# controlador_automa_o_granja.net
KiCad netlist of a schematic drawn in EAGLE
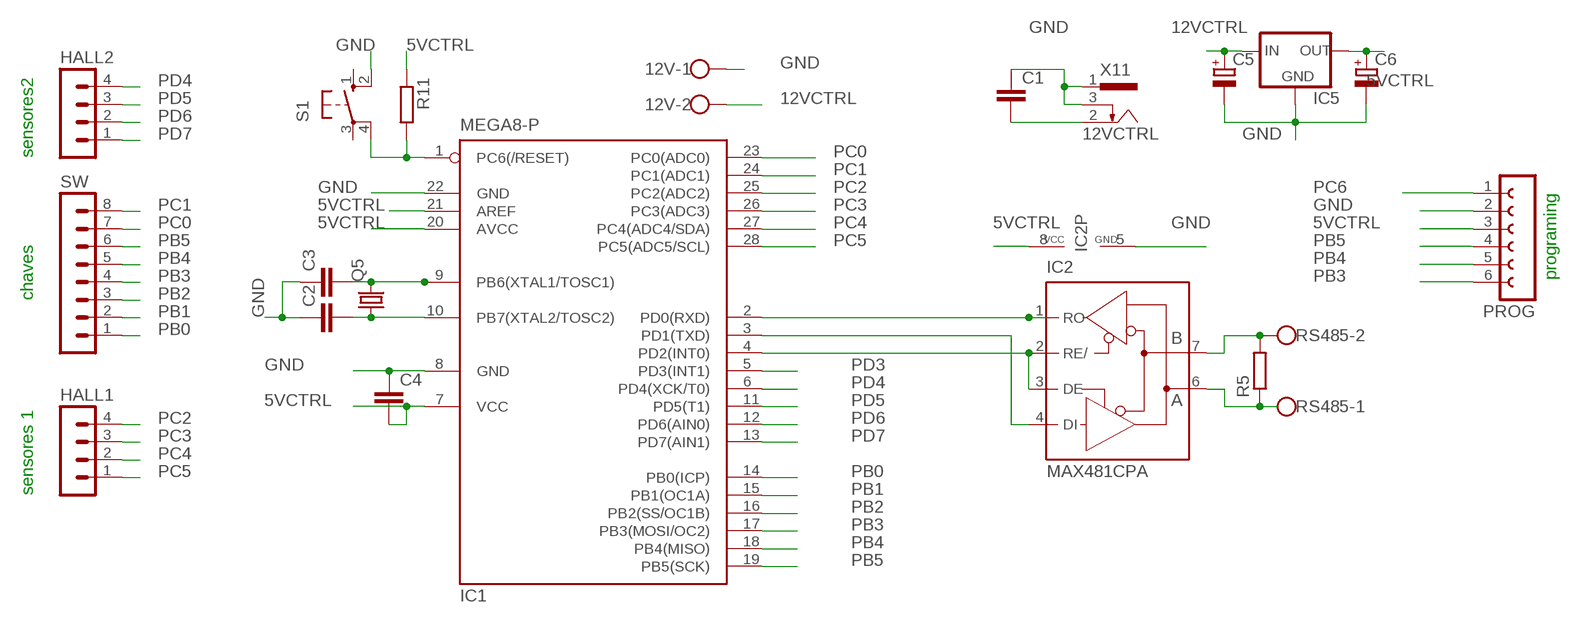
[diagram p0: schematic, sheet 1]

(export (version "E")
  (design (tool "Eeschema 10.0.6"))
  (components
    (comp (ref "12V")
      (value "W237-102")
      (footprint "eagle-import:W237-102")
      (fields (field (name "MPN") "237-102"))
      (libsource (lib "eagle-import") (part "W237-102"))
    )
    (comp (ref "C1")
      (value "C-EU050-025X075")
      (footprint "eagle-import:C050-025X075")
      (libsource (lib "eagle-import") (part "C-EU050-025X075"))
    )
    (comp (ref "C2")
      (value "C-EU050-025X075")
      (footprint "eagle-import:C050-025X075")
      (libsource (lib "eagle-import") (part "C-EU050-025X075"))
    )
    (comp (ref "C3")
      (value "C-EU050-024X044")
      (footprint "eagle-import:C050-024X044")
      (libsource (lib "eagle-import") (part "C-EU050-024X044"))
    )
    (comp (ref "C4")
      (value "C-EU050-024X044")
      (footprint "eagle-import:C050-024X044")
      (libsource (lib "eagle-import") (part "resistor_C-EU050-024X044"))
    )
    (comp (ref "C5")
      (value "CPOL-EUE1.8-4")
      (footprint "eagle-import:E1,8-4")
      (libsource (lib "eagle-import") (part "CPOL-EUE1.8-4"))
    )
    (comp (ref "C6")
      (value "CPOL-EUE1.8-4")
      (footprint "eagle-import:E1,8-4")
      (libsource (lib "eagle-import") (part "CPOL-EUE1.8-4"))
    )
    (comp (ref "HALL1")
      (value "MA04-1")
      (footprint "eagle-import:MA04-1")
      (libsource (lib "eagle-import") (part "MA04-1"))
    )
    (comp (ref "HALL2")
      (value "MA04-1")
      (footprint "eagle-import:MA04-1")
      (libsource (lib "eagle-import") (part "MA04-1"))
    )
    (comp (ref "IC1")
      (value "MEGA8-P")
      (footprint "eagle-import:DIL28-3")
      (libsource (lib "eagle-import") (part "MEGA8-P"))
    )
    (comp (ref "IC2")
      (value "MAX481CPA")
      (footprint "eagle-import:DIL08")
      (fields (field (name "MPN") "MAX481CPA+"))
      (libsource (lib "eagle-import") (part "MAX481CPA"))
    )
    (comp (ref "IC5")
      (value "78LXX")
      (footprint "eagle-import:78LXX")
      (libsource (lib "eagle-import") (part "78LXX"))
    )
    (comp (ref "PROG")
      (value "FE06-1")
      (footprint "eagle-import:FE06")
      (libsource (lib "eagle-import") (part "FE06-1"))
    )
    (comp (ref "Q5")
      (value "CRYSTALHC49S")
      (footprint "eagle-import:HC49_S")
      (libsource (lib "eagle-import") (part "CRYSTALHC49S"))
    )
    (comp (ref "R5")
      (value "R-EU_0207/7")
      (footprint "eagle-import:0207_7")
      (libsource (lib "eagle-import") (part "R-EU_0207/7"))
    )
    (comp (ref "R11")
      (value "R-EU_0207/7")
      (footprint "eagle-import:0207_7")
      (libsource (lib "eagle-import") (part "R-EU_0207/7"))
    )
    (comp (ref "RS485")
      (value "W237-102")
      (footprint "eagle-import:W237-102")
      (fields (field (name "MPN") "237-102"))
      (libsource (lib "eagle-import") (part "W237-102"))
    )
    (comp (ref "S1")
      (value "10-XX")
      (footprint "eagle-import:B3F-10XX")
      (fields (field (name "MPN") "B3F-1000"))
      (libsource (lib "eagle-import") (part "10-XX"))
    )
    (comp (ref "SW")
      (value "MA08-1")
      (footprint "eagle-import:MA08-1")
      (libsource (lib "eagle-import") (part "MA08-1"))
    )
    (comp (ref "X11")
      (value "733980-62")
      (footprint "eagle-import:733980-62")
      (libsource (lib "eagle-import") (part "73398?0-62"))
    )
  )
  (nets
    (net (code "1") (name "/5VCTRL") (class "Default")
      (node (ref "C4") (pin "2") (pinfunction "2_2") (pintype "passive"))
      (node (ref "C6") (pin "+") (pinfunction "+_+") (pintype "passive"))
      (node (ref "IC1") (pin "20") (pinfunction "AVCC_20") (pintype "power_in"))
      (node (ref "IC1") (pin "21") (pinfunction "AREF_21") (pintype "passive"))
      (node (ref "IC1") (pin "7") (pinfunction "VCC_7") (pintype "power_in"))
      (node (ref "IC2") (pin "8") (pinfunction "VCC_8") (pintype "power_in"))
      (node (ref "IC5") (pin "OUT") (pinfunction "OUT_OUT") (pintype "passive"))
      (node (ref "PROG") (pin "3") (pinfunction "3_3") (pintype "passive"))
      (node (ref "R11") (pin "1") (pinfunction "1_1") (pintype "passive"))
    )
    (net (code "2") (name "/12VCTRL") (class "Default")
      (node (ref "12V") (pin "2") (pinfunction "KL_2") (pintype "passive"))
      (node (ref "C1") (pin "2") (pinfunction "2_2") (pintype "passive"))
      (node (ref "C5") (pin "+") (pinfunction "+_+") (pintype "passive"))
      (node (ref "IC5") (pin "IN") (pinfunction "IN_IN") (pintype "input"))
      (node (ref "X11") (pin "2") (pinfunction "2_2") (pintype "passive"))
    )
    (net (code "3") (name "/GND") (class "Default")
      (node (ref "12V") (pin "1") (pinfunction "KL_1") (pintype "passive"))
      (node (ref "C1") (pin "1") (pinfunction "1_1") (pintype "passive"))
      (node (ref "C2") (pin "1") (pinfunction "1_1") (pintype "passive"))
      (node (ref "C3") (pin "1") (pinfunction "1_1") (pintype "passive"))
      (node (ref "C4") (pin "1") (pinfunction "1_1") (pintype "passive"))
      (node (ref "C5") (pin "-") (pinfunction "-_-") (pintype "passive"))
      (node (ref "C6") (pin "-") (pinfunction "-_-") (pintype "passive"))
      (node (ref "IC1") (pin "22") (pinfunction "GND_22") (pintype "power_in"))
      (node (ref "IC1") (pin "8") (pinfunction "GND_8") (pintype "power_in"))
      (node (ref "IC2") (pin "5") (pinfunction "GND_5") (pintype "power_in"))
      (node (ref "IC5") (pin "GND") (pinfunction "GND_GND") (pintype "input"))
      (node (ref "PROG") (pin "2") (pinfunction "2_2") (pintype "passive"))
      (node (ref "S1") (pin "2") (pinfunction "S1_2") (pintype "passive"))
      (node (ref "X11") (pin "1") (pinfunction "1_1") (pintype "passive"))
      (node (ref "X11") (pin "3") (pinfunction "3_3") (pintype "passive"))
    )
    (net (code "4") (name "/PB0") (class "Default")
      (node (ref "IC1") (pin "14") (pinfunction "PB0(ICP)_14") (pintype "bidirectional"))
      (node (ref "SW") (pin "1") (pinfunction "1_1") (pintype "passive"))
    )
    (net (code "5") (name "/PB1") (class "Default")
      (node (ref "IC1") (pin "15") (pinfunction "PB1(OC1A)_15") (pintype "bidirectional"))
      (node (ref "SW") (pin "2") (pinfunction "2_2") (pintype "passive"))
    )
    (net (code "6") (name "/PB2") (class "Default")
      (node (ref "IC1") (pin "16") (pinfunction "PB2(SS/OC1B)_16") (pintype "bidirectional"))
      (node (ref "SW") (pin "3") (pinfunction "3_3") (pintype "passive"))
    )
    (net (code "7") (name "/PB3") (class "Default")
      (node (ref "IC1") (pin "17") (pinfunction "PB3(MOSI/OC2)_17") (pintype "bidirectional"))
      (node (ref "PROG") (pin "6") (pinfunction "6_6") (pintype "passive"))
      (node (ref "SW") (pin "4") (pinfunction "4_4") (pintype "passive"))
    )
    (net (code "8") (name "/PB4") (class "Default")
      (node (ref "IC1") (pin "18") (pinfunction "PB4(MISO)_18") (pintype "bidirectional"))
      (node (ref "PROG") (pin "5") (pinfunction "5_5") (pintype "passive"))
      (node (ref "SW") (pin "5") (pinfunction "5_5") (pintype "passive"))
    )
    (net (code "9") (name "/PB5") (class "Default")
      (node (ref "IC1") (pin "19") (pinfunction "PB5(SCK)_19") (pintype "bidirectional"))
      (node (ref "PROG") (pin "4") (pinfunction "4_4") (pintype "passive"))
      (node (ref "SW") (pin "6") (pinfunction "6_6") (pintype "passive"))
    )
    (net (code "10") (name "/PC0") (class "Default")
      (node (ref "IC1") (pin "23") (pinfunction "PC0(ADC0)_23") (pintype "bidirectional"))
      (node (ref "SW") (pin "7") (pinfunction "7_7") (pintype "passive"))
    )
    (net (code "11") (name "/PC1") (class "Default")
      (node (ref "IC1") (pin "24") (pinfunction "PC1(ADC1)_24") (pintype "bidirectional"))
      (node (ref "SW") (pin "8") (pinfunction "8_8") (pintype "passive"))
    )
    (net (code "12") (name "/PC2") (class "Default")
      (node (ref "HALL1") (pin "4") (pinfunction "4_4") (pintype "passive"))
      (node (ref "IC1") (pin "25") (pinfunction "PC2(ADC2)_25") (pintype "bidirectional"))
    )
    (net (code "13") (name "/PC3") (class "Default")
      (node (ref "HALL1") (pin "3") (pinfunction "3_3") (pintype "passive"))
      (node (ref "IC1") (pin "26") (pinfunction "PC3(ADC3)_26") (pintype "bidirectional"))
    )
    (net (code "14") (name "/PC4") (class "Default")
      (node (ref "HALL1") (pin "2") (pinfunction "2_2") (pintype "passive"))
      (node (ref "IC1") (pin "27") (pinfunction "PC4(ADC4/SDA)_27") (pintype "bidirectional"))
    )
    (net (code "15") (name "/PC5") (class "Default")
      (node (ref "HALL1") (pin "1") (pinfunction "1_1") (pintype "passive"))
      (node (ref "IC1") (pin "28") (pinfunction "PC5(ADC5/SCL)_28") (pintype "bidirectional"))
    )
    (net (code "16") (name "/PC6") (class "Default")
      (node (ref "IC1") (pin "1") (pinfunction "PC6(/RESET)_1") (pintype "bidirectional"))
      (node (ref "PROG") (pin "1") (pinfunction "1_1") (pintype "passive"))
      (node (ref "R11") (pin "2") (pinfunction "2_2") (pintype "passive"))
      (node (ref "S1") (pin "4") (pinfunction "P1_4") (pintype "passive"))
    )
    (net (code "17") (name "/PD3") (class "Default")
      (node (ref "IC1") (pin "5") (pinfunction "PD3(INT1)_5") (pintype "bidirectional"))
    )
    (net (code "18") (name "/PD4") (class "Default")
      (node (ref "HALL2") (pin "4") (pinfunction "4_4") (pintype "passive"))
      (node (ref "IC1") (pin "6") (pinfunction "PD4(XCK/T0)_6") (pintype "bidirectional"))
    )
    (net (code "19") (name "/PD5") (class "Default")
      (node (ref "HALL2") (pin "3") (pinfunction "3_3") (pintype "passive"))
      (node (ref "IC1") (pin "11") (pinfunction "PD5(T1)_11") (pintype "bidirectional"))
    )
    (net (code "20") (name "/PD6") (class "Default")
      (node (ref "HALL2") (pin "2") (pinfunction "2_2") (pintype "passive"))
      (node (ref "IC1") (pin "12") (pinfunction "PD6(AIN0)_12") (pintype "bidirectional"))
    )
    (net (code "21") (name "/PD7") (class "Default")
      (node (ref "HALL2") (pin "1") (pinfunction "1_1") (pintype "passive"))
      (node (ref "IC1") (pin "13") (pinfunction "PD7(AIN1)_13") (pintype "bidirectional"))
    )
    (net (code "22") (name "Net-(IC1-PB6(XTAL1{slash}TOSC1))") (class "Default")
      (node (ref "C3") (pin "2") (pinfunction "2_2") (pintype "passive"))
      (node (ref "IC1") (pin "9") (pinfunction "PB6(XTAL1/TOSC1)_9") (pintype "bidirectional"))
      (node (ref "Q5") (pin "2") (pinfunction "2_2") (pintype "passive"))
    )
    (net (code "23") (name "Net-(IC1-PB7(XTAL2{slash}TOSC2))") (class "Default")
      (node (ref "C2") (pin "2") (pinfunction "2_2") (pintype "passive"))
      (node (ref "IC1") (pin "10") (pinfunction "PB7(XTAL2/TOSC2)_10") (pintype "bidirectional"))
      (node (ref "Q5") (pin "1") (pinfunction "1_1") (pintype "passive"))
    )
    (net (code "24") (name "Net-(IC1-PD0(RXD))") (class "Default")
      (node (ref "IC1") (pin "2") (pinfunction "PD0(RXD)_2") (pintype "bidirectional"))
      (node (ref "IC2") (pin "1") (pinfunction "RO_1") (pintype "output"))
    )
    (net (code "25") (name "Net-(IC1-PD1(TXD))") (class "Default")
      (node (ref "IC1") (pin "3") (pinfunction "PD1(TXD)_3") (pintype "bidirectional"))
      (node (ref "IC2") (pin "4") (pinfunction "DI_4") (pintype "input"))
    )
    (net (code "26") (name "Net-(IC1-PD2(INT0))") (class "Default")
      (node (ref "IC1") (pin "4") (pinfunction "PD2(INT0)_4") (pintype "bidirectional"))
      (node (ref "IC2") (pin "2") (pinfunction "RE/_2") (pintype "input"))
      (node (ref "IC2") (pin "3") (pinfunction "DE_3") (pintype "input"))
    )
    (net (code "27") (name "Net-(IC2A-A)") (class "Default")
      (node (ref "IC2") (pin "6") (pinfunction "A_6") (pintype "passive"))
      (node (ref "R5") (pin "1") (pinfunction "1_1") (pintype "passive"))
      (node (ref "RS485") (pin "1") (pinfunction "KL_1") (pintype "passive"))
    )
    (net (code "28") (name "Net-(IC2A-B)") (class "Default")
      (node (ref "IC2") (pin "7") (pinfunction "B_7") (pintype "passive"))
      (node (ref "R5") (pin "2") (pinfunction "2_2") (pintype "passive"))
      (node (ref "RS485") (pin "2") (pinfunction "KL_2") (pintype "passive"))
    )
    (net (code "29") (name "unconnected-(S1-P-Pad3)") (class "Default")
      (node (ref "S1") (pin "3") (pinfunction "P_3") (pintype "passive"))
    )
    (net (code "30") (name "unconnected-(S1-S-Pad1)") (class "Default")
      (node (ref "S1") (pin "1") (pinfunction "S_1") (pintype "passive"))
    )
  )
)
